# load-cal-board-1point2in.net
KiCad netlist of a schematic drawn in Altium Designer
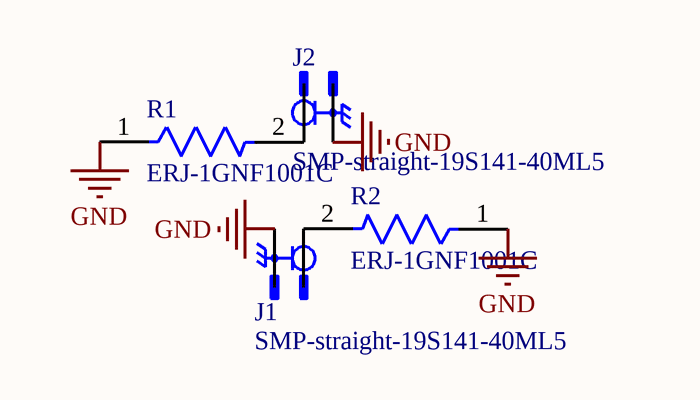
[diagram p0: load-cal-board-1point2in.SchDoc]

(export (version "E")
  (design (tool "Eeschema 10.0.6"))
  (components
    (comp (ref "J1")
      (value "SMP-straight-19S141-40ML5")
      (footprint "rosenberger-19S141-40ML5")
      (description "SMP Connector Plug, Male Pin 50Ohm Surface Mount Solder")
      (fields (field (name "MP") "853050232") (field (name "MF") "Molex"))
      (libsource (lib "") (part "SMP-straight-19S141-40ML5_1"))
    )
    (comp (ref "J2")
      (value "SMP-straight-19S141-40ML5")
      (footprint "rosenberger-19S141-40ML5")
      (description "SMP Connector Plug, Male Pin 50Ohm Surface Mount Solder")
      (fields (field (name "MP") "853050232") (field (name "MF") "Molex"))
      (libsource (lib "SchlibLafe") (part "SMP-straight-19S141-40ML5"))
    )
    (comp (ref "R1")
      (value "ERJ-1GNF1001C")
      (footprint "FP-ERJ1GN-IPC_C")
      (description "RES SMD 1K OHM 1% 1/20W 0201")
      (fields (field (name "TOLERANCE") "1%"))
      (libsource (lib "Altium Content Vault") (part "1029c3af85768c4190bb7ad29bc67b5"))
    )
    (comp (ref "R2")
      (value "ERJ-1GNF1001C")
      (footprint "FP-ERJ1GN-IPC_C")
      (description "RES SMD 1K OHM 1% 1/20W 0201")
      (fields (field (name "TOLERANCE") "1%"))
      (libsource (lib "Altium Content Vault") (part "1029c3af85768c4190bb7ad29bc67b5"))
    )
  )
  (nets
    (net (code "1") (name "GND") (class "Default")
      (node (ref "J1") (pin "gnd") (pinfunction "gnd_gnd") (pintype "passive"))
      (node (ref "J2") (pin "gnd") (pinfunction "gnd_gnd") (pintype "passive"))
      (node (ref "R1") (pin "1") (pinfunction "1_1") (pintype "passive"))
      (node (ref "R2") (pin "1") (pinfunction "1_1") (pintype "passive"))
    )
    (net (code "2") (name "Net-(J1-Pad1)") (class "Default")
      (node (ref "J1") (pin "1") (pinfunction "1_1") (pintype "passive"))
      (node (ref "R2") (pin "2") (pinfunction "2_2") (pintype "passive"))
    )
    (net (code "3") (name "Net-(J2-Pad1)") (class "Default")
      (node (ref "J2") (pin "1") (pinfunction "1_1") (pintype "passive"))
      (node (ref "R1") (pin "2") (pinfunction "2_2") (pintype "passive"))
    )
  )
)
